# Interfaz_digital.net
KiCad netlist of a schematic drawn in Altium Designer
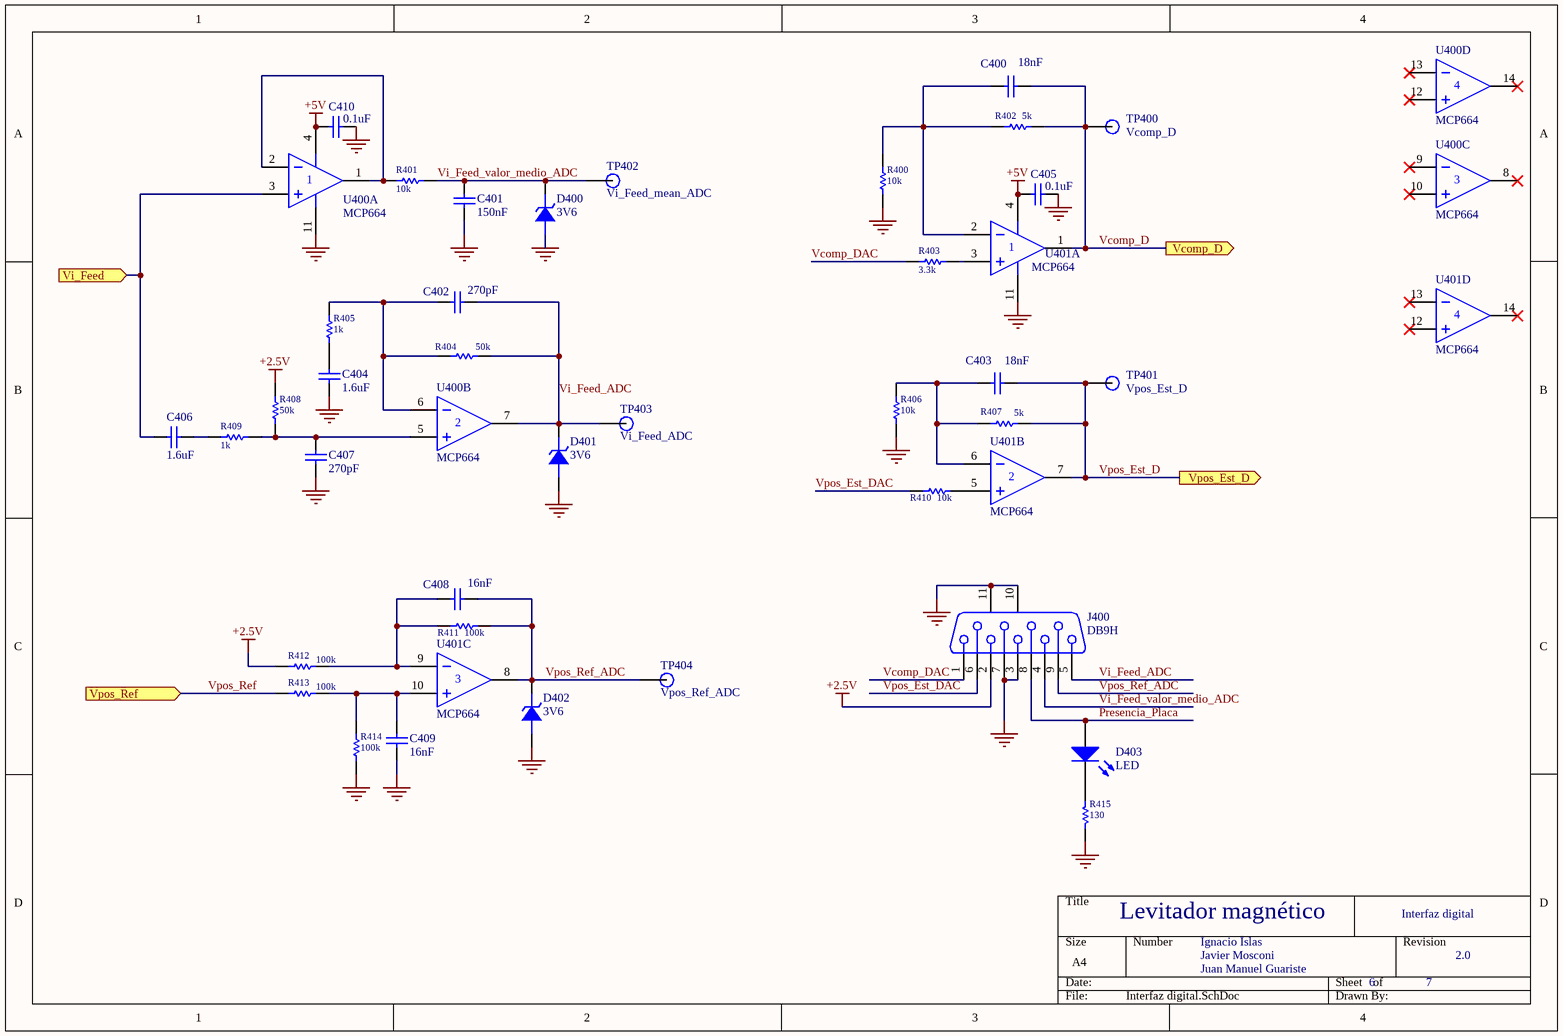
[diagram p0: Interfaz digital.SchDoc]

(export (version "E")
  (design (tool "Eeschema 10.0.6"))
  (components
    (comp (ref "C400")
      (value "18nF")
      (footprint "C1206")
      (description "CAP CER 0.018UF 100V X7R 1206")
      (fields (field (name "MANUFACTURER") "KEMET") (field (name "Comment") "Capacitor"))
      (libsource (lib "Levitador_GMI") (part "Capacitor"))
    )
    (comp (ref "C401")
      (value "150nF")
      (footprint "C1206")
      (description "CAP CER 0.15UF 50V X7R 1206")
      (fields (field (name "MANUFACTURER") "KYOCERA AVX") (field (name "Comment") "Capacitor"))
      (libsource (lib "Levitador_GMI") (part "Capacitor"))
    )
    (comp (ref "C402")
      (value "270pF")
      (footprint "C1206")
      (description "CAP CER 270PF 50V C0G/NP0 1206")
      (fields (field (name "MANUFACTURER") "KEMET") (field (name "Comment") "Capacitor"))
      (libsource (lib "Levitador_GMI") (part "Capacitor"))
    )
    (comp (ref "C403")
      (value "18nF")
      (footprint "C1206")
      (description "CAP CER 0.018UF 100V X7R 1206")
      (fields (field (name "MANUFACTURER") "KEMET") (field (name "Comment") "Capacitor"))
      (libsource (lib "Levitador_GMI") (part "Capacitor"))
    )
    (comp (ref "C404")
      (value "1.6uF")
      (footprint "C1206")
      (description "CAP CER 1.5UF 10V X7R 1206")
      (fields (field (name "MANUFACTURER") "YAGEO") (field (name "Comment") "Capacitor"))
      (libsource (lib "Levitador_GMI") (part "Capacitor"))
    )
    (comp (ref "C405")
      (value "0.1uF")
      (footprint "C1206")
      (description "CAP CER 0.1UF 50V X7R 1206")
      (fields (field (name "MANUFACTURER") "Venkel") (field (name "Comment") "Capacitor"))
      (libsource (lib "Levitador_GMI") (part "Capacitor"))
    )
    (comp (ref "C406")
      (value "1.6uF")
      (footprint "C1206")
      (description "CAP CER 1.5UF 10V X7R 1206")
      (fields (field (name "MANUFACTURER") "YAGEO") (field (name "Comment") "Capacitor"))
      (libsource (lib "Levitador_GMI") (part "Capacitor"))
    )
    (comp (ref "C407")
      (value "270pF")
      (footprint "C1206")
      (description "CAP CER 270PF 50V C0G/NP0 1206")
      (fields (field (name "MANUFACTURER") "KEMET") (field (name "Comment") "Capacitor"))
      (libsource (lib "Levitador_GMI") (part "Capacitor"))
    )
    (comp (ref "C408")
      (value "16nF")
      (footprint "C1206")
      (description "CAP CER 0.016UF 50V C0G/NP0 1206")
      (fields (field (name "MANUFACTURER") "Murata Electronics") (field (name "Comment") "Capacitor"))
      (libsource (lib "Levitador_GMI") (part "Capacitor"))
    )
    (comp (ref "C409")
      (value "16nF")
      (footprint "C1206")
      (description "CAP CER 0.016UF 50V C0G/NP0 1206")
      (fields (field (name "MANUFACTURER") "Murata Electronics") (field (name "Comment") "Capacitor"))
      (libsource (lib "Levitador_GMI") (part "Capacitor"))
    )
    (comp (ref "C410")
      (value "0.1uF")
      (footprint "C1206")
      (description "CAP CER 0.1UF 50V X7R 1206")
      (fields (field (name "MANUFACTURER") "Venkel") (field (name "Comment") "Capacitor"))
      (libsource (lib "Levitador_GMI") (part "Capacitor"))
    )
    (comp (ref "D400")
      (value "3V6")
      (footprint "SMB")
      (description "DIODE ZENER 3.6V 3W SMB")
      (fields (field (name "MANUFACTURER") "onsemi") (field (name "Comment") "Diodo Zener"))
      (libsource (lib "Levitador_GMI") (part "Diodo Zener"))
    )
    (comp (ref "D401")
      (value "3V6")
      (footprint "SMB")
      (description "DIODE ZENER 3.6V 3W SMB")
      (fields (field (name "MANUFACTURER") "onsemi") (field (name "Comment") "Diodo Zener"))
      (libsource (lib "Levitador_GMI") (part "Diodo Zener"))
    )
    (comp (ref "D402")
      (value "3V6")
      (footprint "SMB")
      (description "DIODE ZENER 3.6V 3W SMB")
      (fields (field (name "MANUFACTURER") "onsemi") (field (name "Comment") "Diodo Zener"))
      (libsource (lib "Levitador_GMI") (part "Diodo Zener"))
    )
    (comp (ref "D403")
      (value "LED")
      (footprint "LED 1206 RED")
      (description "1206 RED SMD LED")
      (fields (field (name "MANUFACTURER") "American Opto Plus LED"))
      (libsource (lib "Levitador_GMI") (part "LED"))
    )
    (comp (ref "J400")
      (value "DB9H")
      (footprint "DB9H")
      (description "CONN D-SUB RCPT 9POS R/A SLDR")
      (fields (field (name "MANUFACTURER") "Assmann WSW Components"))
      (libsource (lib "Levitador_GMI") (part "DB9H"))
    )
    (comp (ref "R400")
      (value "10k")
      (footprint "Levitador_GMI:R1206")
      (description "RES 10K OHM 1% 1/4W 1206")
      (fields (field (name "MANUFACTURER") "YAGEO") (field (name "TOLERANCE") "1%"))
      (libsource (lib "Levitador_GMI") (part "R1206"))
    )
    (comp (ref "R401")
      (value "10k")
      (footprint "Levitador_GMI:R1206")
      (description "RES 10K OHM 1% 1/4W 1206")
      (fields (field (name "MANUFACTURER") "YAGEO") (field (name "TOLERANCE") "1%"))
      (libsource (lib "Levitador_GMI") (part "R1206"))
    )
    (comp (ref "R402")
      (value "5k")
      (footprint "Levitador_GMI:R1206")
      (description "RES SMD 5K OHM 1% 0.3W 1206")
      (fields
        (field (name "MANUFACTURER") "Vishay Foil Resistors (Division of Vishay Precision Group)")
        (field (name "TOLERANCE") "1%")
      )
      (libsource (lib "Levitador_GMI") (part "R1206"))
    )
    (comp (ref "R403")
      (value "3.3k")
      (footprint "Levitador_GMI:R1206")
      (description "RES SMD 3.3K OHM 1% 3/4W 1206")
      (fields (field (name "MANUFACTURER") "Vishay Dale") (field (name "TOLERANCE") "1%"))
      (libsource (lib "Levitador_GMI") (part "R1206"))
    )
    (comp (ref "R404")
      (value "50k")
      (footprint "Levitador_GMI:R1206")
      (description "RES SMD 50K OHM 0.1% 1/4W 1206")
      (fields (field (name "MANUFACTURER") "YAGEO") (field (name "TOLERANCE") "0.1%"))
      (libsource (lib "Levitador_GMI") (part "R1206"))
    )
    (comp (ref "R405")
      (value "1k")
      (footprint "Levitador_GMI:R1206")
      (description "RES 1K OHM 1% 1/4W 1206")
      (fields (field (name "MANUFACTURER") "Stackpole Electronics Inc") (field (name "TOLERANCE") "1%"))
      (libsource (lib "Levitador_GMI") (part "R1206"))
    )
    (comp (ref "R406")
      (value "10k")
      (footprint "Levitador_GMI:R1206")
      (description "RES 10K OHM 1% 1/4W 1206")
      (fields (field (name "MANUFACTURER") "YAGEO") (field (name "TOLERANCE") "1%"))
      (libsource (lib "Levitador_GMI") (part "R1206"))
    )
    (comp (ref "R407")
      (value "5k")
      (footprint "Levitador_GMI:R1206")
      (description "RES SMD 5K OHM 1% 0.3W 1206")
      (fields
        (field (name "MANUFACTURER") "Vishay Foil Resistors (Division of Vishay Precision Group)")
        (field (name "TOLERANCE") "1%")
      )
      (libsource (lib "Levitador_GMI") (part "R1206"))
    )
    (comp (ref "R408")
      (value "50k")
      (footprint "Levitador_GMI:R1206")
      (description "RES SMD 50K OHM 0.1% 1/4W 1206")
      (fields (field (name "MANUFACTURER") "YAGEO") (field (name "TOLERANCE") "0.1%"))
      (libsource (lib "Levitador_GMI") (part "R1206"))
    )
    (comp (ref "R409")
      (value "1k")
      (footprint "Levitador_GMI:R1206")
      (description "RES 1K OHM 1% 1/4W 1206")
      (fields (field (name "MANUFACTURER") "Stackpole Electronics Inc") (field (name "TOLERANCE") "1%"))
      (libsource (lib "Levitador_GMI") (part "R1206"))
    )
    (comp (ref "R410")
      (value "10k")
      (footprint "Levitador_GMI:R1206")
      (description "RES 10K OHM 1% 1/4W 1206")
      (fields (field (name "MANUFACTURER") "YAGEO") (field (name "TOLERANCE") "1%"))
      (libsource (lib "Levitador_GMI") (part "R1206"))
    )
    (comp (ref "R411")
      (value "100k")
      (footprint "Levitador_GMI:R1206")
      (description "RES 100K OHM 1% 1/4W 1206")
      (fields (field (name "MANUFACTURER") "Stackpole Electronics Inc") (field (name "TOLERANCE") "1%"))
      (libsource (lib "Levitador_GMI") (part "R1206"))
    )
    (comp (ref "R412")
      (value "100k")
      (footprint "Levitador_GMI:R1206")
      (description "RES 100K OHM 1% 1/4W 1206")
      (fields (field (name "MANUFACTURER") "Stackpole Electronics Inc") (field (name "TOLERANCE") "1%"))
      (libsource (lib "Levitador_GMI") (part "R1206"))
    )
    (comp (ref "R413")
      (value "100k")
      (footprint "Levitador_GMI:R1206")
      (description "RES 100K OHM 1% 1/4W 1206")
      (fields (field (name "MANUFACTURER") "Stackpole Electronics Inc") (field (name "TOLERANCE") "1%"))
      (libsource (lib "Levitador_GMI") (part "R1206"))
    )
    (comp (ref "R414")
      (value "100k")
      (footprint "Levitador_GMI:R1206")
      (description "RES 100K OHM 1% 1/4W 1206")
      (fields (field (name "MANUFACTURER") "Stackpole Electronics Inc") (field (name "TOLERANCE") "1%"))
      (libsource (lib "Levitador_GMI") (part "R1206"))
    )
    (comp (ref "R415")
      (value "130")
      (footprint "Levitador_GMI:R1206")
      (description "RES 130 OHM 1% 1/4W 1206")
      (fields (field (name "MANUFACTURER") "Stackpole Electronics Inc") (field (name "TOLERANCE") "1%"))
      (libsource (lib "Levitador_GMI") (part "R1206"))
    )
    (comp (ref "TP400")
      (value "Vcomp_D")
      (footprint "TestPoint Keystone 5000 Silver-Red")
      (description "PC TEST POINT MINIATURE RED")
      (fields (field (name "MANUFACTURER") "Keystone Electronics"))
      (libsource (lib "Levitador_GMI") (part "Testpoint"))
    )
    (comp (ref "TP401")
      (value "Vpos_Est_D")
      (footprint "TestPoint Keystone 5000 Silver-Red")
      (description "PC TEST POINT MINIATURE RED")
      (fields (field (name "MANUFACTURER") "Keystone Electronics"))
      (libsource (lib "Levitador_GMI") (part "Testpoint"))
    )
    (comp (ref "TP402")
      (value "Vi_Feed_mean_ADC")
      (footprint "TestPoint Keystone 5000 Silver-Red")
      (description "PC TEST POINT MINIATURE RED")
      (fields (field (name "MANUFACTURER") "Keystone Electronics"))
      (libsource (lib "Levitador_GMI") (part "Testpoint"))
    )
    (comp (ref "TP403")
      (value "Vi_Feed_ADC")
      (footprint "TestPoint Keystone 5000 Silver-Red")
      (description "PC TEST POINT MINIATURE RED")
      (fields (field (name "MANUFACTURER") "Keystone Electronics"))
      (libsource (lib "Levitador_GMI") (part "Testpoint"))
    )
    (comp (ref "TP404")
      (value "Vpos_Ref_ADC")
      (footprint "TestPoint Keystone 5000 Silver-Red")
      (description "PC TEST POINT MINIATURE RED")
      (fields (field (name "MANUFACTURER") "Keystone Electronics"))
      (libsource (lib "Levitador_GMI") (part "Testpoint"))
    )
    (comp (ref "U400")
      (value "MCP664")
      (footprint "SOIC14")
      (description "IC OPAMP GP 4 CIRCUIT 14TSSOP")
      (fields (field (name "MANUFACTURER") "Microchip Technology"))
      (libsource (lib "Levitador_GMI") (part "MCP664"))
    )
    (comp (ref "U401")
      (value "MCP664")
      (footprint "SOIC14")
      (description "IC OPAMP GP 4 CIRCUIT 14TSSOP")
      (fields (field (name "MANUFACTURER") "Microchip Technology"))
      (libsource (lib "Levitador_GMI") (part "MCP664"))
    )
  )
  (nets
    (net (code "1") (name "+2.5V") (class "Default")
      (node (ref "J400") (pin "2") (pinfunction "2_2") (pintype "passive"))
      (node (ref "R408") (pin "2") (pinfunction "2_2") (pintype "passive"))
      (node (ref "R412") (pin "1") (pinfunction "1_1") (pintype "passive"))
    )
    (net (code "2") (name "+5V") (class "Default")
      (node (ref "C405") (pin "1") (pinfunction "1_1") (pintype "passive"))
      (node (ref "C410") (pin "1") (pinfunction "1_1") (pintype "passive"))
      (node (ref "U400") (pin "4") (pinfunction "V+_4") (pintype "power_in"))
      (node (ref "U401") (pin "4") (pinfunction "V+_4") (pintype "power_in"))
    )
    (net (code "3") (name "/Presencia_Placa") (class "Default")
      (node (ref "D403") (pin "1") (pinfunction "A_1") (pintype "passive"))
      (node (ref "J400") (pin "8") (pinfunction "8_8") (pintype "passive"))
    )
    (net (code "4") (name "/Vcomp_D") (class "Default")
      (node (ref "C400") (pin "1") (pinfunction "1_1") (pintype "passive"))
      (node (ref "R402") (pin "2") (pinfunction "2_2") (pintype "passive"))
      (node (ref "TP400") (pin "1") (pinfunction "1_1") (pintype "passive"))
      (node (ref "U401") (pin "1") (pinfunction "OUT_1") (pintype "passive"))
    )
    (net (code "5") (name "/Vcomp_DAC") (class "Default")
      (node (ref "J400") (pin "1") (pinfunction "1_1") (pintype "passive"))
      (node (ref "R403") (pin "1") (pinfunction "1_1") (pintype "passive"))
    )
    (net (code "6") (name "/Vi_Feed") (class "Default")
      (node (ref "C406") (pin "1") (pinfunction "1_1") (pintype "passive"))
      (node (ref "U400") (pin "3") (pinfunction "IN+_3") (pintype "passive"))
    )
    (net (code "7") (name "/Vi_Feed_ADC") (class "Default")
      (node (ref "C402") (pin "1") (pinfunction "1_1") (pintype "passive"))
      (node (ref "D401") (pin "2") (pinfunction "2_2") (pintype "passive"))
      (node (ref "J400") (pin "5") (pinfunction "5_5") (pintype "passive"))
      (node (ref "R404") (pin "2") (pinfunction "2_2") (pintype "passive"))
      (node (ref "TP403") (pin "1") (pinfunction "1_1") (pintype "passive"))
      (node (ref "U400") (pin "7") (pinfunction "OUT_7") (pintype "passive"))
    )
    (net (code "8") (name "/Vi_Feed_valor_medio_ADC") (class "Default")
      (node (ref "C401") (pin "2") (pinfunction "2_2") (pintype "passive"))
      (node (ref "D400") (pin "2") (pinfunction "2_2") (pintype "passive"))
      (node (ref "J400") (pin "4") (pinfunction "4_4") (pintype "passive"))
      (node (ref "R401") (pin "2") (pinfunction "2_2") (pintype "passive"))
      (node (ref "TP402") (pin "1") (pinfunction "1_1") (pintype "passive"))
    )
    (net (code "9") (name "/Vpos_Est_D") (class "Default")
      (node (ref "C403") (pin "1") (pinfunction "1_1") (pintype "passive"))
      (node (ref "R407") (pin "2") (pinfunction "2_2") (pintype "passive"))
      (node (ref "TP401") (pin "1") (pinfunction "1_1") (pintype "passive"))
      (node (ref "U401") (pin "7") (pinfunction "OUT_7") (pintype "passive"))
    )
    (net (code "10") (name "/Vpos_Est_DAC") (class "Default")
      (node (ref "J400") (pin "6") (pinfunction "6_6") (pintype "passive"))
      (node (ref "R410") (pin "1") (pinfunction "1_1") (pintype "passive"))
    )
    (net (code "11") (name "/Vpos_Ref") (class "Default")
      (node (ref "R413") (pin "1") (pinfunction "1_1") (pintype "passive"))
    )
    (net (code "12") (name "/Vpos_Ref_ADC") (class "Default")
      (node (ref "C408") (pin "1") (pinfunction "1_1") (pintype "passive"))
      (node (ref "D402") (pin "2") (pinfunction "2_2") (pintype "passive"))
      (node (ref "J400") (pin "9") (pinfunction "9_9") (pintype "passive"))
      (node (ref "R411") (pin "2") (pinfunction "2_2") (pintype "passive"))
      (node (ref "TP404") (pin "1") (pinfunction "1_1") (pintype "passive"))
      (node (ref "U401") (pin "8") (pinfunction "OUT_8") (pintype "passive"))
    )
    (net (code "13") (name "GND") (class "Default")
      (node (ref "C401") (pin "1") (pinfunction "1_1") (pintype "passive"))
      (node (ref "C404") (pin "2") (pinfunction "2_2") (pintype "passive"))
      (node (ref "C405") (pin "2") (pinfunction "2_2") (pintype "passive"))
      (node (ref "C407") (pin "1") (pinfunction "1_1") (pintype "passive"))
      (node (ref "C409") (pin "2") (pinfunction "2_2") (pintype "passive"))
      (node (ref "C410") (pin "2") (pinfunction "2_2") (pintype "passive"))
      (node (ref "D400") (pin "1") (pinfunction "1_1") (pintype "passive"))
      (node (ref "D401") (pin "1") (pinfunction "1_1") (pintype "passive"))
      (node (ref "D402") (pin "1") (pinfunction "1_1") (pintype "passive"))
      (node (ref "J400") (pin "10") (pinfunction "MH1_10") (pintype "passive"))
      (node (ref "J400") (pin "11") (pinfunction "MH2_11") (pintype "passive"))
      (node (ref "J400") (pin "3") (pinfunction "3_3") (pintype "passive"))
      (node (ref "J400") (pin "7") (pinfunction "7_7") (pintype "passive"))
      (node (ref "R400") (pin "1") (pinfunction "1_1") (pintype "passive"))
      (node (ref "R406") (pin "1") (pinfunction "1_1") (pintype "passive"))
      (node (ref "R414") (pin "1") (pinfunction "1_1") (pintype "passive"))
      (node (ref "R415") (pin "1") (pinfunction "1_1") (pintype "passive"))
      (node (ref "U400") (pin "11") (pinfunction "V-_11") (pintype "power_in"))
      (node (ref "U401") (pin "11") (pinfunction "V-_11") (pintype "power_in"))
    )
    (net (code "14") (name "Net-(C404-Pad1)") (class "Default")
      (node (ref "C404") (pin "1") (pinfunction "1_1") (pintype "passive"))
      (node (ref "R405") (pin "1") (pinfunction "1_1") (pintype "passive"))
    )
    (net (code "15") (name "Net-(C406-Pad2)") (class "Default")
      (node (ref "C406") (pin "2") (pinfunction "2_2") (pintype "passive"))
      (node (ref "R409") (pin "1") (pinfunction "1_1") (pintype "passive"))
    )
    (net (code "16") (name "Net-(D403-K)") (class "Default")
      (node (ref "D403") (pin "2") (pinfunction "K_2") (pintype "passive"))
      (node (ref "R415") (pin "2") (pinfunction "2_2") (pintype "passive"))
    )
    (net (code "17") (name "Net-(U400A-IN-)") (class "Default")
      (node (ref "R401") (pin "1") (pinfunction "1_1") (pintype "passive"))
      (node (ref "U400") (pin "1") (pinfunction "OUT_1") (pintype "passive"))
      (node (ref "U400") (pin "2") (pinfunction "IN-_2") (pintype "passive"))
    )
    (net (code "18") (name "Net-(U400B-IN+)") (class "Default")
      (node (ref "C407") (pin "2") (pinfunction "2_2") (pintype "passive"))
      (node (ref "R408") (pin "1") (pinfunction "1_1") (pintype "passive"))
      (node (ref "R409") (pin "2") (pinfunction "2_2") (pintype "passive"))
      (node (ref "U400") (pin "5") (pinfunction "IN+_5") (pintype "passive"))
    )
    (net (code "19") (name "Net-(U400B-IN-)") (class "Default")
      (node (ref "C402") (pin "2") (pinfunction "2_2") (pintype "passive"))
      (node (ref "R404") (pin "1") (pinfunction "1_1") (pintype "passive"))
      (node (ref "R405") (pin "2") (pinfunction "2_2") (pintype "passive"))
      (node (ref "U400") (pin "6") (pinfunction "IN-_6") (pintype "passive"))
    )
    (net (code "20") (name "Net-(U401A-IN+)") (class "Default")
      (node (ref "R403") (pin "2") (pinfunction "2_2") (pintype "passive"))
      (node (ref "U401") (pin "3") (pinfunction "IN+_3") (pintype "passive"))
    )
    (net (code "21") (name "Net-(U401A-IN-)") (class "Default")
      (node (ref "C400") (pin "2") (pinfunction "2_2") (pintype "passive"))
      (node (ref "R400") (pin "2") (pinfunction "2_2") (pintype "passive"))
      (node (ref "R402") (pin "1") (pinfunction "1_1") (pintype "passive"))
      (node (ref "U401") (pin "2") (pinfunction "IN-_2") (pintype "passive"))
    )
    (net (code "22") (name "Net-(U401B-IN+)") (class "Default")
      (node (ref "R410") (pin "2") (pinfunction "2_2") (pintype "passive"))
      (node (ref "U401") (pin "5") (pinfunction "IN+_5") (pintype "passive"))
    )
    (net (code "23") (name "Net-(U401B-IN-)") (class "Default")
      (node (ref "C403") (pin "2") (pinfunction "2_2") (pintype "passive"))
      (node (ref "R406") (pin "2") (pinfunction "2_2") (pintype "passive"))
      (node (ref "R407") (pin "1") (pinfunction "1_1") (pintype "passive"))
      (node (ref "U401") (pin "6") (pinfunction "IN-_6") (pintype "passive"))
    )
    (net (code "24") (name "Net-(U401C-IN+)") (class "Default")
      (node (ref "C409") (pin "1") (pinfunction "1_1") (pintype "passive"))
      (node (ref "R413") (pin "2") (pinfunction "2_2") (pintype "passive"))
      (node (ref "R414") (pin "2") (pinfunction "2_2") (pintype "passive"))
      (node (ref "U401") (pin "10") (pinfunction "IN+_10") (pintype "passive"))
    )
    (net (code "25") (name "Net-(U401C-IN-)") (class "Default")
      (node (ref "C408") (pin "2") (pinfunction "2_2") (pintype "passive"))
      (node (ref "R411") (pin "1") (pinfunction "1_1") (pintype "passive"))
      (node (ref "R412") (pin "2") (pinfunction "2_2") (pintype "passive"))
      (node (ref "U401") (pin "9") (pinfunction "IN-_9") (pintype "passive"))
    )
    (net (code "26") (name "unconnected-(U400C-IN+-Pad10)") (class "Default")
      (node (ref "U400") (pin "10") (pinfunction "IN+_10") (pintype "passive+no_connect"))
    )
    (net (code "27") (name "unconnected-(U400C-IN--Pad9)") (class "Default")
      (node (ref "U400") (pin "9") (pinfunction "IN-_9") (pintype "passive+no_connect"))
    )
    (net (code "28") (name "unconnected-(U400C-OUT-Pad8)") (class "Default")
      (node (ref "U400") (pin "8") (pinfunction "OUT_8") (pintype "passive+no_connect"))
    )
    (net (code "29") (name "unconnected-(U400D-IN+-Pad12)") (class "Default")
      (node (ref "U400") (pin "12") (pinfunction "IN+_12") (pintype "passive+no_connect"))
    )
    (net (code "30") (name "unconnected-(U400D-IN--Pad13)") (class "Default")
      (node (ref "U400") (pin "13") (pinfunction "IN-_13") (pintype "passive+no_connect"))
    )
    (net (code "31") (name "unconnected-(U400D-OUT-Pad14)") (class "Default")
      (node (ref "U400") (pin "14") (pinfunction "OUT_14") (pintype "passive+no_connect"))
    )
    (net (code "32") (name "unconnected-(U401D-IN+-Pad12)") (class "Default")
      (node (ref "U401") (pin "12") (pinfunction "IN+_12") (pintype "passive+no_connect"))
    )
    (net (code "33") (name "unconnected-(U401D-IN--Pad13)") (class "Default")
      (node (ref "U401") (pin "13") (pinfunction "IN-_13") (pintype "passive+no_connect"))
    )
    (net (code "34") (name "unconnected-(U401D-OUT-Pad14)") (class "Default")
      (node (ref "U401") (pin "14") (pinfunction "OUT_14") (pintype "passive+no_connect"))
    )
  )
)
